# Radii.net
KiCad netlist of a schematic drawn in EAGLE
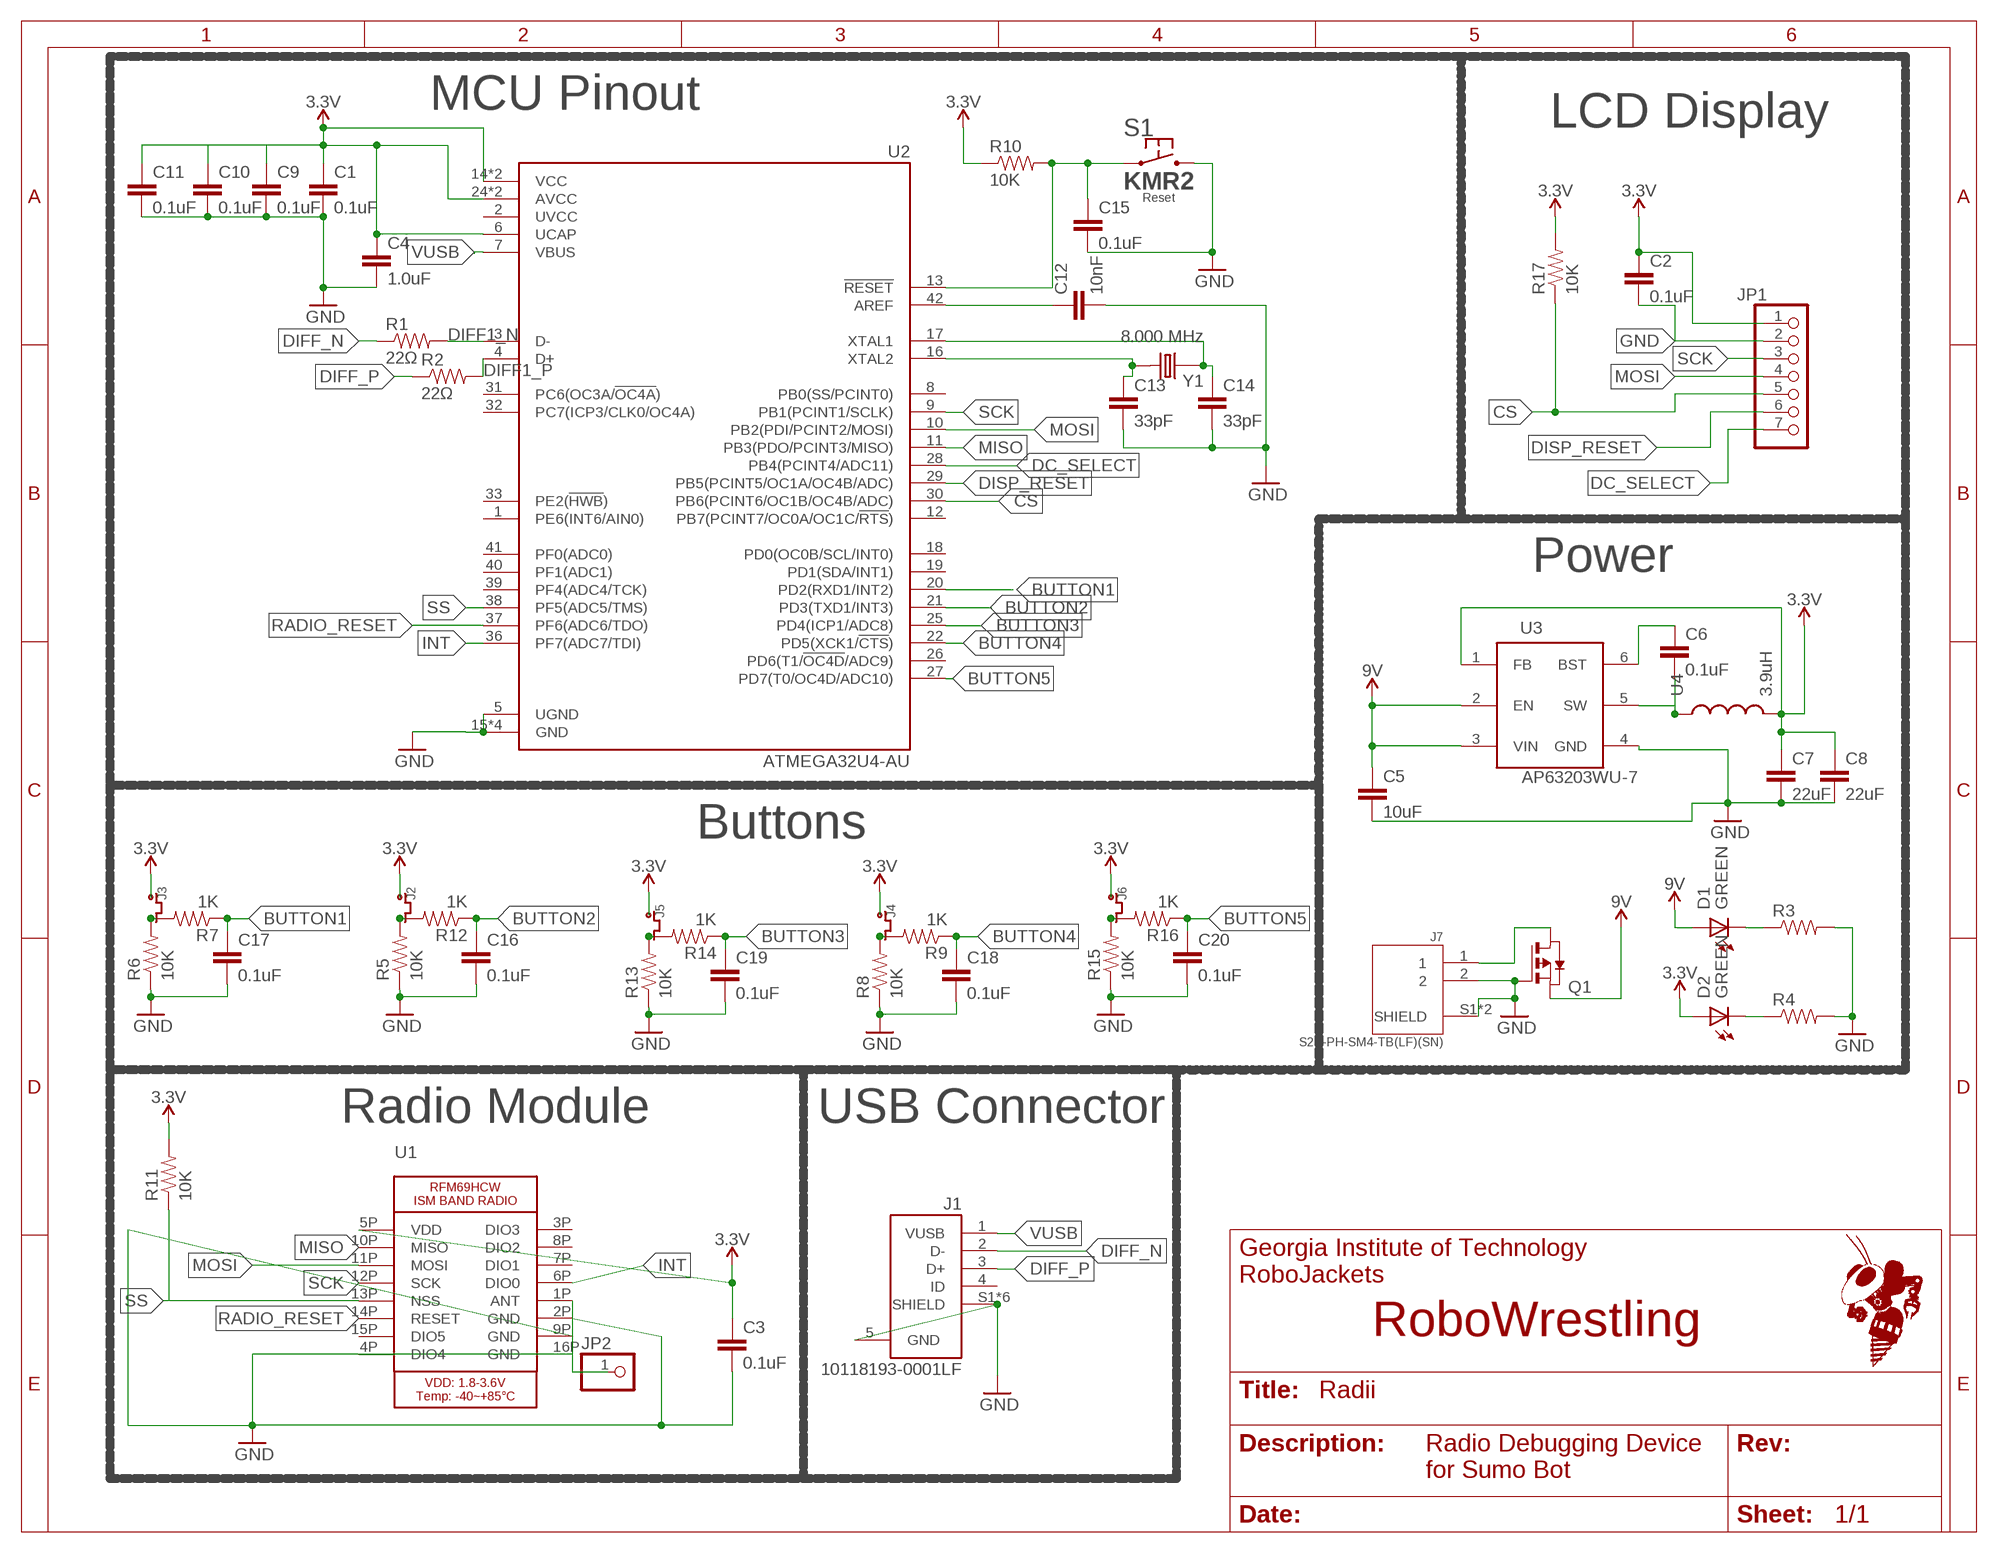
[diagram p0: schematic, sheet 1]

(export (version "E")
  (design (tool "Eeschema 10.0.6"))
  (components
    (comp (ref "C1")
      (value "0.1uF")
      (footprint "eagle-import:0603")
      (libsource (lib "eagle-import") (part "0.1UF-0603-25V-(+80/-20%)"))
    )
    (comp (ref "C2")
      (value "0.1uF")
      (footprint "eagle-import:0603")
      (libsource (lib "eagle-import") (part "0.1UF-0603-25V-(+80/-20%)"))
    )
    (comp (ref "C3")
      (value "0.1uF")
      (footprint "eagle-import:0603")
      (libsource (lib "eagle-import") (part "0.1UF-0603-25V-(+80/-20%)"))
    )
    (comp (ref "C4")
      (value "1.0uF")
      (footprint "eagle-import:0603")
      (libsource (lib "eagle-import") (part "1.0UF-0603-16V-10%"))
    )
    (comp (ref "C5")
      (value "10uF")
      (footprint "eagle-import:0603")
      (libsource (lib "eagle-import") (part "10UF-0603-6.3V-20%"))
    )
    (comp (ref "C6")
      (value "0.1uF")
      (footprint "eagle-import:0603")
      (libsource (lib "eagle-import") (part "0.1UF-0603-25V-(+80/-20%)"))
    )
    (comp (ref "C7")
      (value "22uF")
      (footprint "eagle-import:1210")
      (libsource (lib "eagle-import") (part "22UF-1210-16V-20%"))
    )
    (comp (ref "C8")
      (value "22uF")
      (footprint "eagle-import:1210")
      (libsource (lib "eagle-import") (part "22UF-1210-16V-20%"))
    )
    (comp (ref "C9")
      (value "0.1uF")
      (footprint "eagle-import:0603")
      (libsource (lib "eagle-import") (part "0.1UF-0603-25V-(+80/-20%)"))
    )
    (comp (ref "C10")
      (value "0.1uF")
      (footprint "eagle-import:0603")
      (libsource (lib "eagle-import") (part "0.1UF-0603-25V-(+80/-20%)"))
    )
    (comp (ref "C11")
      (value "0.1uF")
      (footprint "eagle-import:0603")
      (libsource (lib "eagle-import") (part "0.1UF-0603-25V-(+80/-20%)"))
    )
    (comp (ref "C12")
      (value "10nF")
      (footprint "eagle-import:0603")
      (libsource (lib "eagle-import") (part "10NF-0603-50V-10%"))
    )
    (comp (ref "C13")
      (value "33pF")
      (footprint "eagle-import:0603")
      (libsource (lib "eagle-import") (part "33PF-0603-50V-5%"))
    )
    (comp (ref "C14")
      (value "33pF")
      (footprint "eagle-import:0603")
      (libsource (lib "eagle-import") (part "33PF-0603-50V-5%"))
    )
    (comp (ref "C15")
      (value "0.1uF")
      (footprint "eagle-import:0603")
      (libsource (lib "eagle-import") (part "0.1UF-0603-25V-(+80/-20%)"))
    )
    (comp (ref "C16")
      (value "0.1uF")
      (footprint "eagle-import:0603")
      (libsource (lib "eagle-import") (part "0.1UF-0603-25V-(+80/-20%)"))
    )
    (comp (ref "C17")
      (value "0.1uF")
      (footprint "eagle-import:0603")
      (libsource (lib "eagle-import") (part "0.1UF-0603-25V-(+80/-20%)"))
    )
    (comp (ref "C18")
      (value "0.1uF")
      (footprint "eagle-import:0603")
      (libsource (lib "eagle-import") (part "0.1UF-0603-25V-(+80/-20%)"))
    )
    (comp (ref "C19")
      (value "0.1uF")
      (footprint "eagle-import:0603")
      (libsource (lib "eagle-import") (part "0.1UF-0603-25V-(+80/-20%)"))
    )
    (comp (ref "C20")
      (value "0.1uF")
      (footprint "eagle-import:0603")
      (libsource (lib "eagle-import") (part "0.1UF-0603-25V-(+80/-20%)"))
    )
    (comp (ref "D1")
      (value "GREEN")
      (footprint "eagle-import:CHIP-LED0603")
      (libsource (lib "eagle-import") (part "LED-SMD"))
    )
    (comp (ref "D2")
      (value "GREEN")
      (footprint "eagle-import:CHIP-LED0603")
      (libsource (lib "eagle-import") (part "LED-SMD"))
    )
    (comp (ref "J1")
      (value "10118193-0001LF")
      (footprint "eagle-import:FCI_10118193-0001LF")
      (libsource (lib "eagle-import") (part "10118193-0001LF"))
    )
    (comp (ref "J2")
      (value "BUTTON")
      (footprint "eagle-import:1X02")
      (libsource (lib "eagle-import") (part "BUTTON"))
    )
    (comp (ref "J3")
      (value "BUTTON")
      (footprint "eagle-import:1X02")
      (libsource (lib "eagle-import") (part "BUTTON"))
    )
    (comp (ref "J4")
      (value "BUTTON")
      (footprint "eagle-import:1X02")
      (libsource (lib "eagle-import") (part "BUTTON"))
    )
    (comp (ref "J5")
      (value "BUTTON")
      (footprint "eagle-import:1X02")
      (libsource (lib "eagle-import") (part "BUTTON"))
    )
    (comp (ref "J6")
      (value "BUTTON")
      (footprint "eagle-import:1X02")
      (libsource (lib "eagle-import") (part "BUTTON"))
    )
    (comp (ref "J7")
      (value "S2B-PH-SM4-TB(LF)(SN)")
      (footprint "eagle-import:JST_S2B-PH-SM4-TB(LF)(SN)")
      (fields (field (name "DIGI-KEY_PART_NUMBER") "455-1749-1-ND"))
      (libsource (lib "eagle-import") (part "S2B-PH-SM4-TB(LF)(SN)"))
    )
    (comp (ref "JP1")
      (value "PINHD-1X7")
      (footprint "eagle-import:1X07")
      (libsource (lib "eagle-import") (part "PINHD-1X7"))
    )
    (comp (ref "JP2")
      (value "PINHD-1X1")
      (footprint "eagle-import:1X01")
      (libsource (lib "eagle-import") (part "PINHD-1X1"))
    )
    (comp (ref "Q1")
      (value "PMOS")
      (footprint "eagle-import:SOT-23-3")
      (libsource (lib "eagle-import") (part "PMOS"))
    )
    (comp (ref "R1")
      (value "22Ω")
      (footprint "eagle-import:0603-RES")
      (libsource (lib "eagle-import") (part "22OHM1/10W1%(0603)"))
    )
    (comp (ref "R2")
      (value "22Ω")
      (footprint "eagle-import:0603-RES")
      (libsource (lib "eagle-import") (part "22OHM1/10W1%(0603)"))
    )
    (comp (ref "R3")
      (value "RESISTOR0603")
      (footprint "eagle-import:0603")
      (libsource (lib "eagle-import") (part "RESISTOR0603"))
    )
    (comp (ref "R4")
      (value "RESISTOR0603")
      (footprint "eagle-import:0603")
      (libsource (lib "eagle-import") (part "RESISTOR0603"))
    )
    (comp (ref "R5")
      (value "10K")
      (footprint "eagle-import:0603-RES")
      (libsource (lib "eagle-import") (part "10KOHM-1/10W-1%(0603)0603"))
    )
    (comp (ref "R6")
      (value "10K")
      (footprint "eagle-import:0603-RES")
      (libsource (lib "eagle-import") (part "10KOHM-1/10W-1%(0603)0603"))
    )
    (comp (ref "R7")
      (value "1K")
      (footprint "eagle-import:0603-RES")
      (libsource (lib "eagle-import") (part "10KOHM-1/10W-1%(0603)0603"))
    )
    (comp (ref "R8")
      (value "10K")
      (footprint "eagle-import:0603-RES")
      (libsource (lib "eagle-import") (part "10KOHM-1/10W-1%(0603)0603"))
    )
    (comp (ref "R9")
      (value "1K")
      (footprint "eagle-import:0603-RES")
      (libsource (lib "eagle-import") (part "10KOHM-1/10W-1%(0603)0603"))
    )
    (comp (ref "R10")
      (value "10K")
      (footprint "eagle-import:0603-RES")
      (libsource (lib "eagle-import") (part "10KOHM-1/10W-1%(0603)0603"))
    )
    (comp (ref "R11")
      (value "10K")
      (footprint "eagle-import:0603-RES")
      (libsource (lib "eagle-import") (part "10KOHM-1/10W-1%(0603)0603"))
    )
    (comp (ref "R12")
      (value "1K")
      (footprint "eagle-import:0603-RES")
      (libsource (lib "eagle-import") (part "10KOHM-1/10W-1%(0603)0603"))
    )
    (comp (ref "R13")
      (value "10K")
      (footprint "eagle-import:0603-RES")
      (libsource (lib "eagle-import") (part "10KOHM-1/10W-1%(0603)0603"))
    )
    (comp (ref "R14")
      (value "1K")
      (footprint "eagle-import:0603-RES")
      (libsource (lib "eagle-import") (part "10KOHM-1/10W-1%(0603)0603"))
    )
    (comp (ref "R15")
      (value "10K")
      (footprint "eagle-import:0603-RES")
      (libsource (lib "eagle-import") (part "10KOHM-1/10W-1%(0603)0603"))
    )
    (comp (ref "R16")
      (value "1K")
      (footprint "eagle-import:0603-RES")
      (libsource (lib "eagle-import") (part "10KOHM-1/10W-1%(0603)0603"))
    )
    (comp (ref "R17")
      (value "10K")
      (footprint "eagle-import:0603-RES")
      (libsource (lib "eagle-import") (part "10KOHM-1/10W-1%(0603)0603"))
    )
    (comp (ref "S1")
      (value "KMR2")
      (footprint "eagle-import:KMR2")
      (fields (field (name "FUNCTION") "Reset"))
      (libsource (lib "eagle-import") (part "KMR2"))
    )
    (comp (ref "U1")
      (value "RFM69HCW_SMT")
      (footprint "eagle-import:RFMHCW_SMT")
      (libsource (lib "eagle-import") (part "RFM69HCW_SMT"))
    )
    (comp (ref "U2")
      (value "ATMEGA32U4-AU")
      (footprint "eagle-import:44-TQFP(10X10)")
      (libsource (lib "eagle-import") (part "ATMEGA32U4-AUR"))
    )
    (comp (ref "U3")
      (value "AP63203WU-7")
      (footprint "eagle-import:TSOT-23-6")
      (libsource (lib "eagle-import") (part "AP63203WU-7"))
    )
    (comp (ref "U4")
      (value "3.9uH")
      (footprint "eagle-import:1255AY-3R9N=P3")
      (fields (field (name "TOLERANCE") "±30%"))
      (libsource (lib "eagle-import") (part "1255AY-3R9N=P3"))
    )
    (comp (ref "Y1")
      (value "8.000 MHz")
      (footprint "eagle-import:XTAL_ECS-80-20-5PX-TR")
      (libsource (lib "eagle-import") (part "ECS-80-20-5PX-TR"))
    )
  )
  (nets
    (net (code "1") (name "/DIFF1_N") (class "Default")
      (node (ref "R1") (pin "2") (pinfunction "2_2") (pintype "passive"))
      (node (ref "U2") (pin "3") (pinfunction "D-_3") (pintype "passive"))
    )
    (net (code "2") (name "/DIFF1_P") (class "Default")
      (node (ref "R2") (pin "2") (pinfunction "2_2") (pintype "passive"))
      (node (ref "U2") (pin "4") (pinfunction "D+_4") (pintype "passive"))
    )
    (net (code "3") (name "3.3V") (class "Default")
      (node (ref "C1") (pin "1") (pinfunction "1_1") (pintype "passive"))
      (node (ref "C10") (pin "1") (pinfunction "1_1") (pintype "passive"))
      (node (ref "C11") (pin "1") (pinfunction "1_1") (pintype "passive"))
      (node (ref "C2") (pin "1") (pinfunction "1_1") (pintype "passive"))
      (node (ref "C3") (pin "1") (pinfunction "1_1") (pintype "passive"))
      (node (ref "C4") (pin "1") (pinfunction "1_1") (pintype "passive"))
      (node (ref "C7") (pin "1") (pinfunction "1_1") (pintype "passive"))
      (node (ref "C8") (pin "1") (pinfunction "1_1") (pintype "passive"))
      (node (ref "C9") (pin "1") (pinfunction "1_1") (pintype "passive"))
      (node (ref "D2") (pin "A") (pinfunction "A_A") (pintype "passive"))
      (node (ref "J2") (pin "1") (pinfunction "P$1_1") (pintype "passive"))
      (node (ref "J3") (pin "1") (pinfunction "P$1_1") (pintype "passive"))
      (node (ref "J4") (pin "1") (pinfunction "P$1_1") (pintype "passive"))
      (node (ref "J5") (pin "1") (pinfunction "P$1_1") (pintype "passive"))
      (node (ref "J6") (pin "1") (pinfunction "P$1_1") (pintype "passive"))
      (node (ref "JP1") (pin "1") (pinfunction "1_1") (pintype "passive"))
      (node (ref "R10") (pin "1") (pinfunction "1_1") (pintype "passive"))
      (node (ref "R11") (pin "2") (pinfunction "2_2") (pintype "passive"))
      (node (ref "R17") (pin "2") (pinfunction "2_2") (pintype "passive"))
      (node (ref "U1") (pin "5P") (pinfunction "VDD_5P") (pintype "passive"))
      (node (ref "U2") (pin "14") (pinfunction "VCC_14") (pintype "passive"))
      (node (ref "U2") (pin "24") (pinfunction "AVCC_24") (pintype "passive"))
      (node (ref "U2") (pin "34") (pinfunction "VCC_34") (pintype "passive"))
      (node (ref "U2") (pin "44") (pinfunction "AVCC_44") (pintype "passive"))
      (node (ref "U2") (pin "6") (pinfunction "UCAP_6") (pintype "passive"))
      (node (ref "U3") (pin "1") (pinfunction "FB_1") (pintype "passive"))
      (node (ref "U4") (pin "2") (pinfunction "2_2") (pintype "passive"))
    )
    (net (code "4") (name "9V") (class "Default")
      (node (ref "C5") (pin "1") (pinfunction "1_1") (pintype "passive"))
      (node (ref "D1") (pin "A") (pinfunction "A_A") (pintype "passive"))
      (node (ref "Q1") (pin "2") (pinfunction "S_2") (pintype "passive"))
      (node (ref "U3") (pin "2") (pinfunction "EN_2") (pintype "passive"))
      (node (ref "U3") (pin "3") (pinfunction "VIN_3") (pintype "passive"))
    )
    (net (code "5") (name "BUTTON1") (class "Default")
      (node (ref "C17") (pin "1") (pinfunction "1_1") (pintype "passive"))
      (node (ref "R7") (pin "1") (pinfunction "1_1") (pintype "passive"))
      (node (ref "U2") (pin "20") (pinfunction "PD2(RXD1/INT2)_20") (pintype "passive"))
    )
    (net (code "6") (name "BUTTON2") (class "Default")
      (node (ref "C16") (pin "1") (pinfunction "1_1") (pintype "passive"))
      (node (ref "R12") (pin "1") (pinfunction "1_1") (pintype "passive"))
      (node (ref "U2") (pin "21") (pinfunction "PD3(TXD1/INT3)_21") (pintype "passive"))
    )
    (net (code "7") (name "BUTTON3") (class "Default")
      (node (ref "C19") (pin "1") (pinfunction "1_1") (pintype "passive"))
      (node (ref "R14") (pin "1") (pinfunction "1_1") (pintype "passive"))
      (node (ref "U2") (pin "25") (pinfunction "PD4(ICP1/ADC8)_25") (pintype "passive"))
    )
    (net (code "8") (name "BUTTON4") (class "Default")
      (node (ref "C18") (pin "1") (pinfunction "1_1") (pintype "passive"))
      (node (ref "R9") (pin "1") (pinfunction "1_1") (pintype "passive"))
      (node (ref "U2") (pin "22") (pinfunction "PD5(XCK1/~{CTS})_22") (pintype "passive"))
    )
    (net (code "9") (name "BUTTON5") (class "Default")
      (node (ref "C20") (pin "1") (pinfunction "1_1") (pintype "passive"))
      (node (ref "R16") (pin "1") (pinfunction "1_1") (pintype "passive"))
      (node (ref "U2") (pin "27") (pinfunction "PD7(T0/OC4D/ADC10)_27") (pintype "passive"))
    )
    (net (code "10") (name "CS") (class "Default")
      (node (ref "JP1") (pin "5") (pinfunction "5_5") (pintype "passive"))
      (node (ref "R17") (pin "1") (pinfunction "1_1") (pintype "passive"))
      (node (ref "U2") (pin "30") (pinfunction "PB6(PCINT6/OC1B/OC4B/ADC)_30") (pintype "passive"))
    )
    (net (code "11") (name "DC_SELECT") (class "Default")
      (node (ref "JP1") (pin "7") (pinfunction "7_7") (pintype "passive"))
      (node (ref "U2") (pin "28") (pinfunction "PB4(PCINT4/ADC11)_28") (pintype "passive"))
    )
    (net (code "12") (name "DIFF_N") (class "Default")
      (node (ref "J1") (pin "2") (pinfunction "D-_2") (pintype "passive"))
      (node (ref "R1") (pin "1") (pinfunction "1_1") (pintype "passive"))
    )
    (net (code "13") (name "DIFF_P") (class "Default")
      (node (ref "J1") (pin "3") (pinfunction "D+_3") (pintype "passive"))
      (node (ref "R2") (pin "1") (pinfunction "1_1") (pintype "passive"))
    )
    (net (code "14") (name "DISP_RESET") (class "Default")
      (node (ref "JP1") (pin "6") (pinfunction "6_6") (pintype "passive"))
      (node (ref "U2") (pin "29") (pinfunction "PB5(PCINT5/OC1A/OC4B/ADC)_29") (pintype "passive"))
    )
    (net (code "15") (name "GND") (class "Default")
      (node (ref "C1") (pin "2") (pinfunction "2_2") (pintype "passive"))
      (node (ref "C10") (pin "2") (pinfunction "2_2") (pintype "passive"))
      (node (ref "C11") (pin "2") (pinfunction "2_2") (pintype "passive"))
      (node (ref "C12") (pin "2") (pinfunction "2_2") (pintype "passive"))
      (node (ref "C13") (pin "2") (pinfunction "2_2") (pintype "passive"))
      (node (ref "C14") (pin "2") (pinfunction "2_2") (pintype "passive"))
      (node (ref "C15") (pin "2") (pinfunction "2_2") (pintype "passive"))
      (node (ref "C16") (pin "2") (pinfunction "2_2") (pintype "passive"))
      (node (ref "C17") (pin "2") (pinfunction "2_2") (pintype "passive"))
      (node (ref "C18") (pin "2") (pinfunction "2_2") (pintype "passive"))
      (node (ref "C19") (pin "2") (pinfunction "2_2") (pintype "passive"))
      (node (ref "C2") (pin "2") (pinfunction "2_2") (pintype "passive"))
      (node (ref "C20") (pin "2") (pinfunction "2_2") (pintype "passive"))
      (node (ref "C3") (pin "2") (pinfunction "2_2") (pintype "passive"))
      (node (ref "C4") (pin "2") (pinfunction "2_2") (pintype "passive"))
      (node (ref "C5") (pin "2") (pinfunction "2_2") (pintype "passive"))
      (node (ref "C7") (pin "2") (pinfunction "2_2") (pintype "passive"))
      (node (ref "C8") (pin "2") (pinfunction "2_2") (pintype "passive"))
      (node (ref "C9") (pin "2") (pinfunction "2_2") (pintype "passive"))
      (node (ref "J1") (pin "5") (pinfunction "GND_5") (pintype "passive"))
      (node (ref "J1") (pin "S1") (pinfunction "SHIELD_S1") (pintype "passive"))
      (node (ref "J1") (pin "S2") (pinfunction "SHIELD_S2") (pintype "passive"))
      (node (ref "J1") (pin "S3") (pinfunction "SHIELD_S3") (pintype "passive"))
      (node (ref "J1") (pin "S4") (pinfunction "SHIELD_S4") (pintype "passive"))
      (node (ref "J1") (pin "S5") (pinfunction "SHIELD_S5") (pintype "passive"))
      (node (ref "J1") (pin "S6") (pinfunction "SHIELD_S6") (pintype "passive"))
      (node (ref "J7") (pin "2") (pinfunction "2_2") (pintype "passive"))
      (node (ref "J7") (pin "S1") (pinfunction "SHIELD_S1") (pintype "passive"))
      (node (ref "J7") (pin "S2") (pinfunction "SHIELD_S2") (pintype "passive"))
      (node (ref "JP1") (pin "2") (pinfunction "2_2") (pintype "passive"))
      (node (ref "Q1") (pin "1") (pinfunction "G_1") (pintype "passive"))
      (node (ref "R13") (pin "1") (pinfunction "1_1") (pintype "passive"))
      (node (ref "R15") (pin "1") (pinfunction "1_1") (pintype "passive"))
      (node (ref "R3") (pin "2") (pinfunction "2_2") (pintype "passive"))
      (node (ref "R4") (pin "2") (pinfunction "2_2") (pintype "passive"))
      (node (ref "R5") (pin "1") (pinfunction "1_1") (pintype "passive"))
      (node (ref "R6") (pin "1") (pinfunction "1_1") (pintype "passive"))
      (node (ref "R8") (pin "1") (pinfunction "1_1") (pintype "passive"))
      (node (ref "S1") (pin "2.1") (pinfunction "2_2.1") (pintype "passive"))
      (node (ref "S1") (pin "2.2") (pinfunction "2_2.2") (pintype "passive"))
      (node (ref "U1") (pin "16P") (pinfunction "GND_16P") (pintype "passive"))
      (node (ref "U1") (pin "2P") (pinfunction "GND_2P") (pintype "passive"))
      (node (ref "U1") (pin "9P") (pinfunction "GND_9P") (pintype "passive"))
      (node (ref "U2") (pin "15") (pinfunction "GND_15") (pintype "passive"))
      (node (ref "U2") (pin "23") (pinfunction "GND_23") (pintype "passive"))
      (node (ref "U2") (pin "35") (pinfunction "GND_35") (pintype "passive"))
      (node (ref "U2") (pin "43") (pinfunction "GND_43") (pintype "passive"))
      (node (ref "U2") (pin "5") (pinfunction "UGND_5") (pintype "passive"))
      (node (ref "U3") (pin "4") (pinfunction "GND_4") (pintype "passive"))
    )
    (net (code "16") (name "INT") (class "Default")
      (node (ref "U1") (pin "6P") (pinfunction "DIO0_6P") (pintype "passive"))
      (node (ref "U2") (pin "36") (pinfunction "PF7(ADC7/TDI)_36") (pintype "passive"))
    )
    (net (code "17") (name "MISO") (class "Default")
      (node (ref "U1") (pin "10P") (pinfunction "MISO_10P") (pintype "passive"))
      (node (ref "U2") (pin "11") (pinfunction "PB3(PDO/PCINT3/MISO)_11") (pintype "passive"))
    )
    (net (code "18") (name "MOSI") (class "Default")
      (node (ref "JP1") (pin "4") (pinfunction "4_4") (pintype "passive"))
      (node (ref "U1") (pin "11P") (pinfunction "MOSI_11P") (pintype "passive"))
      (node (ref "U2") (pin "10") (pinfunction "PB2(PDI/PCINT2/MOSI)_10") (pintype "passive"))
    )
    (net (code "19") (name "Net-(D1-K)") (class "Default")
      (node (ref "D1") (pin "C") (pinfunction "K_C") (pintype "passive"))
      (node (ref "R3") (pin "1") (pinfunction "1_1") (pintype "passive"))
    )
    (net (code "20") (name "Net-(D2-K)") (class "Default")
      (node (ref "D2") (pin "C") (pinfunction "K_C") (pintype "passive"))
      (node (ref "R4") (pin "1") (pinfunction "1_1") (pintype "passive"))
    )
    (net (code "21") (name "Net-(J2-P$2)") (class "Default")
      (node (ref "J2") (pin "2") (pinfunction "P$2_2") (pintype "passive"))
      (node (ref "R12") (pin "2") (pinfunction "2_2") (pintype "passive"))
      (node (ref "R5") (pin "2") (pinfunction "2_2") (pintype "passive"))
    )
    (net (code "22") (name "Net-(J3-P$2)") (class "Default")
      (node (ref "J3") (pin "2") (pinfunction "P$2_2") (pintype "passive"))
      (node (ref "R6") (pin "2") (pinfunction "2_2") (pintype "passive"))
      (node (ref "R7") (pin "2") (pinfunction "2_2") (pintype "passive"))
    )
    (net (code "23") (name "Net-(J4-P$2)") (class "Default")
      (node (ref "J4") (pin "2") (pinfunction "P$2_2") (pintype "passive"))
      (node (ref "R8") (pin "2") (pinfunction "2_2") (pintype "passive"))
      (node (ref "R9") (pin "2") (pinfunction "2_2") (pintype "passive"))
    )
    (net (code "24") (name "Net-(J5-P$2)") (class "Default")
      (node (ref "J5") (pin "2") (pinfunction "P$2_2") (pintype "passive"))
      (node (ref "R13") (pin "2") (pinfunction "2_2") (pintype "passive"))
      (node (ref "R14") (pin "2") (pinfunction "2_2") (pintype "passive"))
    )
    (net (code "25") (name "Net-(J6-P$2)") (class "Default")
      (node (ref "J6") (pin "2") (pinfunction "P$2_2") (pintype "passive"))
      (node (ref "R15") (pin "2") (pinfunction "2_2") (pintype "passive"))
      (node (ref "R16") (pin "2") (pinfunction "2_2") (pintype "passive"))
    )
    (net (code "26") (name "Net-(Q1-D)") (class "Default")
      (node (ref "J7") (pin "1") (pinfunction "1_1") (pintype "passive"))
      (node (ref "Q1") (pin "3") (pinfunction "D_3") (pintype "passive"))
    )
    (net (code "27") (name "Net-(U1-ANT)") (class "Default")
      (node (ref "JP2") (pin "1") (pinfunction "1_1") (pintype "passive"))
      (node (ref "U1") (pin "1P") (pinfunction "ANT_1P") (pintype "passive"))
    )
    (net (code "28") (name "Net-(U2-AREF)") (class "Default")
      (node (ref "C12") (pin "1") (pinfunction "1_1") (pintype "passive"))
      (node (ref "U2") (pin "42") (pinfunction "AREF_42") (pintype "passive"))
    )
    (net (code "29") (name "Net-(U2-XTAL1)") (class "Default")
      (node (ref "C14") (pin "1") (pinfunction "1_1") (pintype "passive"))
      (node (ref "U2") (pin "17") (pinfunction "XTAL1_17") (pintype "passive"))
      (node (ref "Y1") (pin "1") (pinfunction "1_1") (pintype "passive"))
    )
    (net (code "30") (name "Net-(U2-XTAL2)") (class "Default")
      (node (ref "C13") (pin "1") (pinfunction "1_1") (pintype "passive"))
      (node (ref "U2") (pin "16") (pinfunction "XTAL2_16") (pintype "passive"))
      (node (ref "Y1") (pin "2") (pinfunction "2_2") (pintype "passive"))
    )
    (net (code "31") (name "Net-(U2-~{RESET})") (class "Default")
      (node (ref "C15") (pin "1") (pinfunction "1_1") (pintype "passive"))
      (node (ref "R10") (pin "2") (pinfunction "2_2") (pintype "passive"))
      (node (ref "S1") (pin "1.1") (pinfunction "1_1.1") (pintype "passive"))
      (node (ref "S1") (pin "1.2") (pinfunction "1_1.2") (pintype "passive"))
      (node (ref "U2") (pin "13") (pinfunction "~{RESET}_13") (pintype "passive"))
    )
    (net (code "32") (name "Net-(U3-BST)") (class "Default")
      (node (ref "C6") (pin "1") (pinfunction "1_1") (pintype "passive"))
      (node (ref "U3") (pin "6") (pinfunction "BST_6") (pintype "passive"))
    )
    (net (code "33") (name "Net-(U3-SW)") (class "Default")
      (node (ref "C6") (pin "2") (pinfunction "2_2") (pintype "passive"))
      (node (ref "U3") (pin "5") (pinfunction "SW_5") (pintype "passive"))
      (node (ref "U4") (pin "1") (pinfunction "1_1") (pintype "passive"))
    )
    (net (code "34") (name "RADIO_RESET") (class "Default")
      (node (ref "U1") (pin "14P") (pinfunction "RESET_14P") (pintype "passive"))
      (node (ref "U2") (pin "37") (pinfunction "PF6(ADC6/TDO)_37") (pintype "passive"))
    )
    (net (code "35") (name "SCK") (class "Default")
      (node (ref "JP1") (pin "3") (pinfunction "3_3") (pintype "passive"))
      (node (ref "U1") (pin "12P") (pinfunction "SCK_12P") (pintype "passive"))
      (node (ref "U2") (pin "9") (pinfunction "PB1(PCINT1/SCLK)_9") (pintype "passive"))
    )
    (net (code "36") (name "SS") (class "Default")
      (node (ref "R11") (pin "1") (pinfunction "1_1") (pintype "passive"))
      (node (ref "U1") (pin "13P") (pinfunction "NSS_13P") (pintype "passive"))
      (node (ref "U2") (pin "38") (pinfunction "PF5(ADC5/TMS)_38") (pintype "passive"))
    )
    (net (code "37") (name "VUSB") (class "Default")
      (node (ref "J1") (pin "1") (pinfunction "VUSB_1") (pintype "passive"))
      (node (ref "U2") (pin "7") (pinfunction "VBUS_7") (pintype "passive"))
    )
    (net (code "38") (name "unconnected-(J1-ID-Pad4)") (class "Default")
      (node (ref "J1") (pin "4") (pinfunction "ID_4") (pintype "passive"))
    )
    (net (code "39") (name "unconnected-(U1-DIO1-Pad7P)") (class "Default")
      (node (ref "U1") (pin "7P") (pinfunction "DIO1_7P") (pintype "passive"))
    )
    (net (code "40") (name "unconnected-(U1-DIO2-Pad8P)") (class "Default")
      (node (ref "U1") (pin "8P") (pinfunction "DIO2_8P") (pintype "passive"))
    )
    (net (code "41") (name "unconnected-(U1-DIO3-Pad3P)") (class "Default")
      (node (ref "U1") (pin "3P") (pinfunction "DIO3_3P") (pintype "passive"))
    )
    (net (code "42") (name "unconnected-(U1-DIO4-Pad4P)") (class "Default")
      (node (ref "U1") (pin "4P") (pinfunction "DIO4_4P") (pintype "passive"))
    )
    (net (code "43") (name "unconnected-(U1-DIO5-Pad15P)") (class "Default")
      (node (ref "U1") (pin "15P") (pinfunction "DIO5_15P") (pintype "passive"))
    )
    (net (code "44") (name "unconnected-(U2-PB0(SS{slash}PCINT0)-Pad8)") (class "Default")
      (node (ref "U2") (pin "8") (pinfunction "PB0(SS/PCINT0)_8") (pintype "passive"))
    )
    (net (code "45") (name "unconnected-(U2-PB7(PCINT7{slash}OC0A{slash}OC1C{slash}~{RTS})-Pad12)") (class "Default")
      (node (ref "U2") (pin "12") (pinfunction "PB7(PCINT7/OC0A/OC1C/~{RTS})_12") (pintype "passive"))
    )
    (net (code "46") (name "unconnected-(U2-PC6(OC3A{slash}~{OC4A})-Pad31)") (class "Default")
      (node (ref "U2") (pin "31") (pinfunction "PC6(OC3A/~{OC4A})_31") (pintype "passive"))
    )
    (net (code "47") (name "unconnected-(U2-PC7(ICP3{slash}CLK0{slash}OC4A)-Pad32)") (class "Default")
      (node (ref "U2") (pin "32") (pinfunction "PC7(ICP3/CLK0/OC4A)_32") (pintype "passive"))
    )
    (net (code "48") (name "unconnected-(U2-PD0(OC0B{slash}SCL{slash}INT0)-Pad18)") (class "Default")
      (node (ref "U2") (pin "18") (pinfunction "PD0(OC0B/SCL/INT0)_18") (pintype "passive"))
    )
    (net (code "49") (name "unconnected-(U2-PD1(SDA{slash}INT1)-Pad19)") (class "Default")
      (node (ref "U2") (pin "19") (pinfunction "PD1(SDA/INT1)_19") (pintype "passive"))
    )
    (net (code "50") (name "unconnected-(U2-PD6(T1{slash}~{OC4D}{slash}ADC9)-Pad26)") (class "Default")
      (node (ref "U2") (pin "26") (pinfunction "PD6(T1/~{OC4D}/ADC9)_26") (pintype "passive"))
    )
    (net (code "51") (name "unconnected-(U2-PE2(~{HWB})-Pad33)") (class "Default")
      (node (ref "U2") (pin "33") (pinfunction "PE2(~{HWB})_33") (pintype "passive"))
    )
    (net (code "52") (name "unconnected-(U2-PE6(INT6{slash}AIN0)-Pad1)") (class "Default")
      (node (ref "U2") (pin "1") (pinfunction "PE6(INT6/AIN0)_1") (pintype "passive"))
    )
    (net (code "53") (name "unconnected-(U2-PF0(ADC0)-Pad41)") (class "Default")
      (node (ref "U2") (pin "41") (pinfunction "PF0(ADC0)_41") (pintype "passive"))
    )
    (net (code "54") (name "unconnected-(U2-PF1(ADC1)-Pad40)") (class "Default")
      (node (ref "U2") (pin "40") (pinfunction "PF1(ADC1)_40") (pintype "passive"))
    )
    (net (code "55") (name "unconnected-(U2-PF4(ADC4{slash}TCK)-Pad39)") (class "Default")
      (node (ref "U2") (pin "39") (pinfunction "PF4(ADC4/TCK)_39") (pintype "passive"))
    )
    (net (code "56") (name "unconnected-(U2-UVCC-Pad2)") (class "Default")
      (node (ref "U2") (pin "2") (pinfunction "UVCC_2") (pintype "passive"))
    )
  )
)
